# Pulser_AD8331.net
KiCad netlist of a schematic drawn in Altium Designer
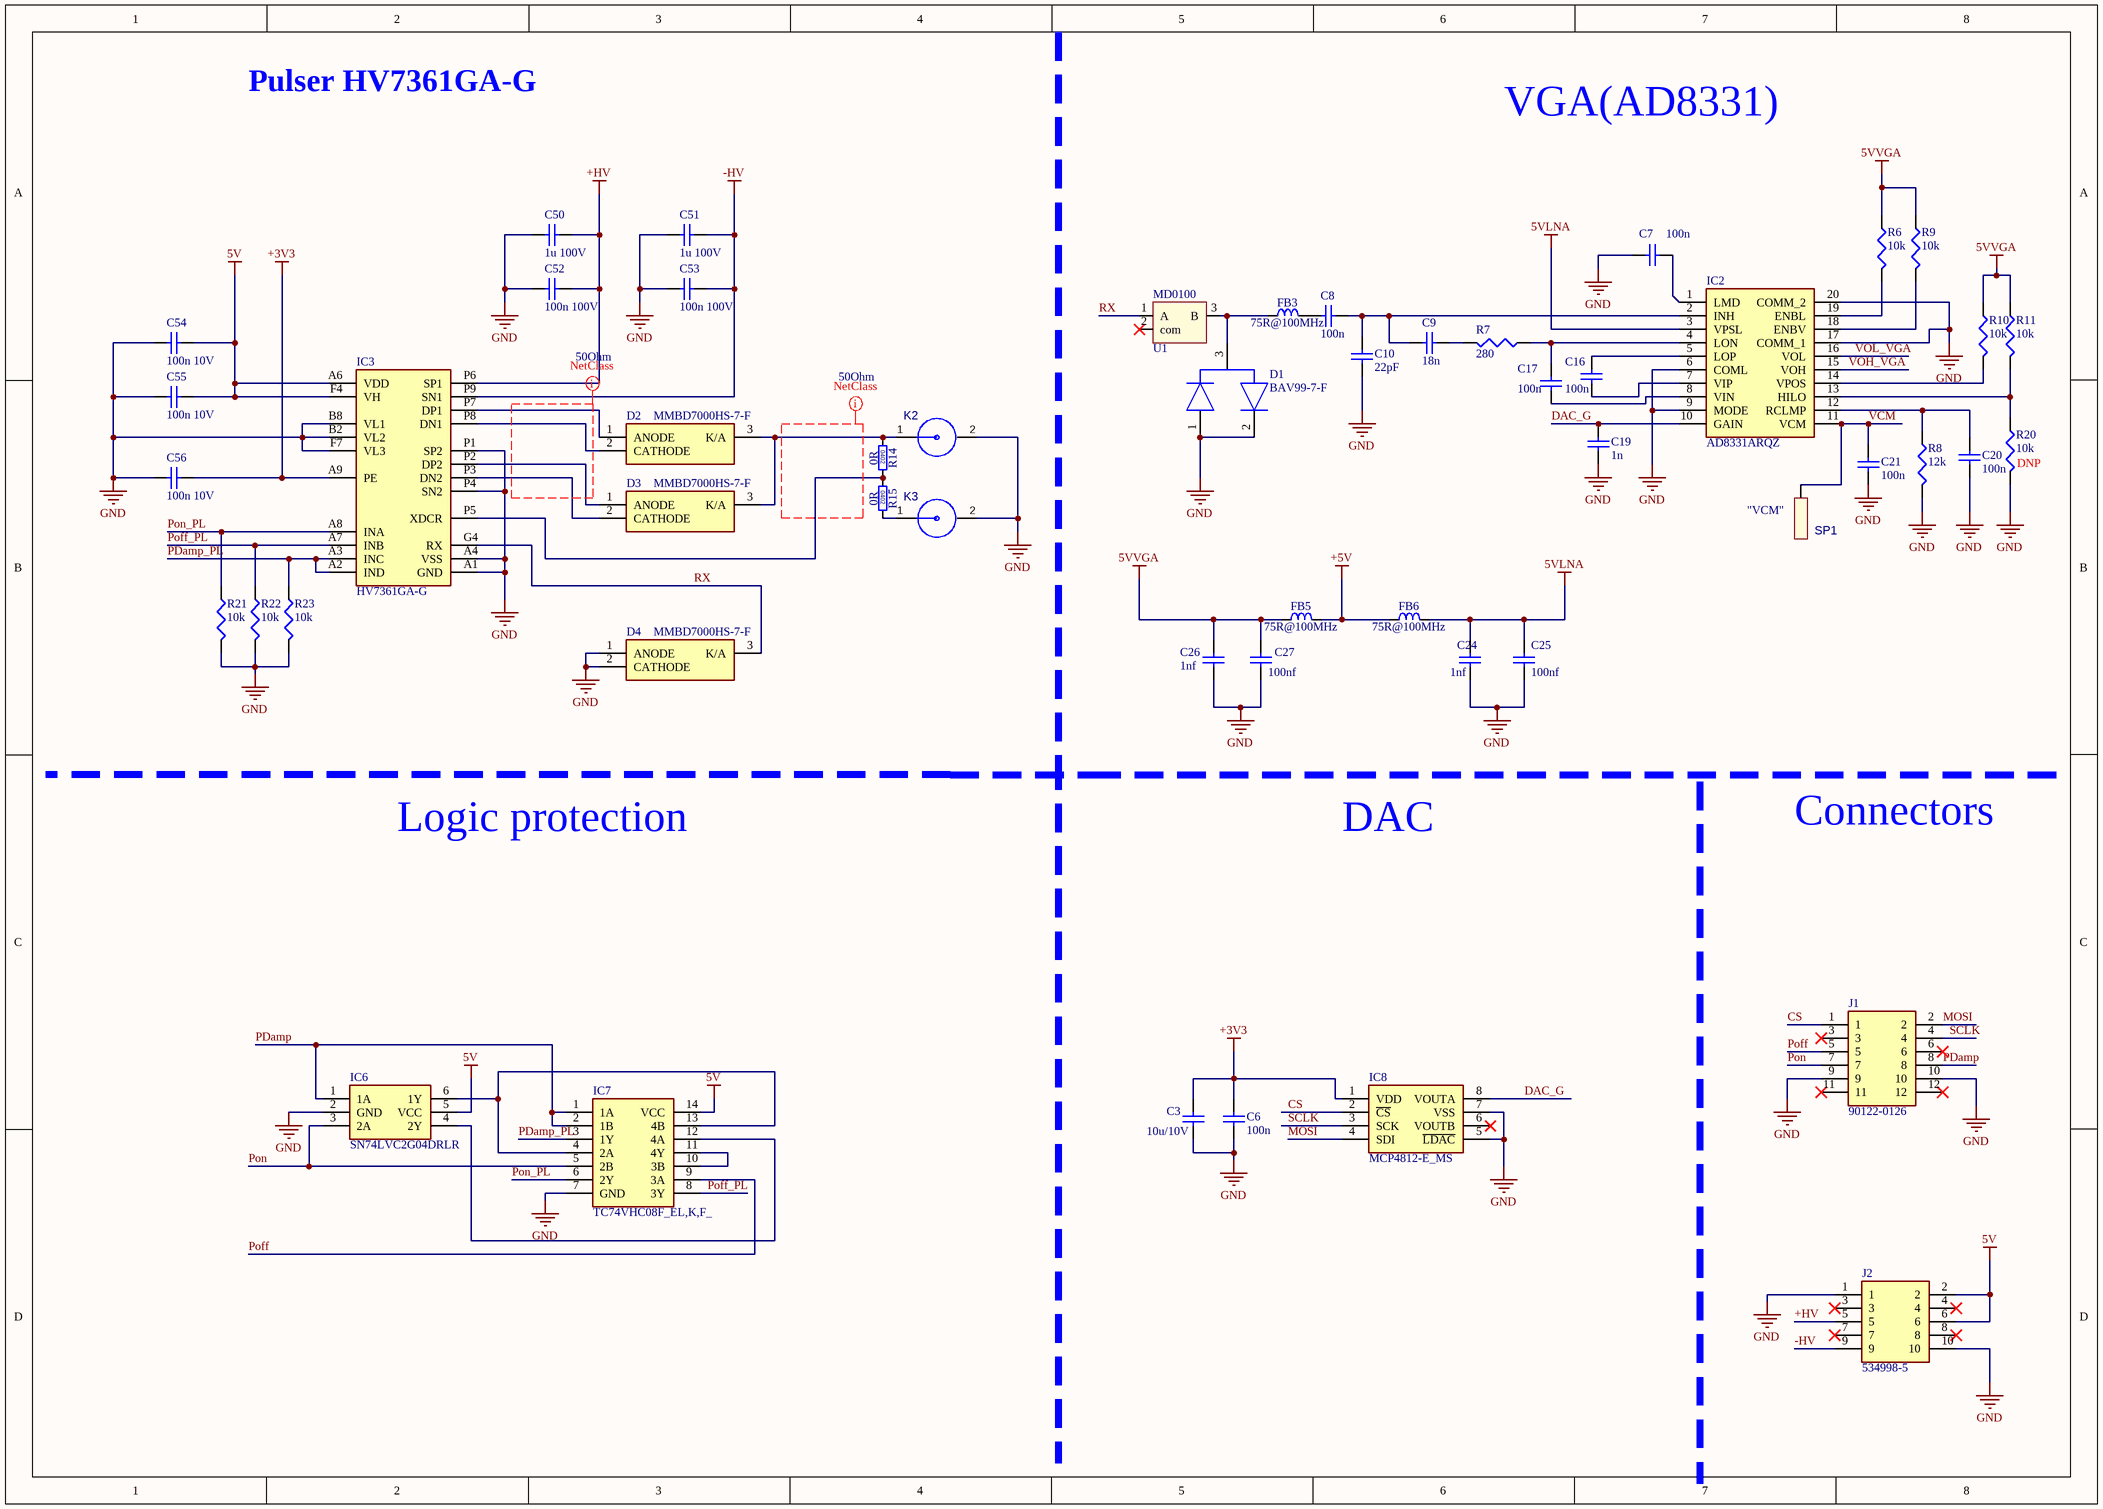
[diagram p0: Pulser & AD8331.SchDoc]

(export (version "E")
  (design (tool "Eeschema 10.0.6"))
  (components
    (comp (ref "C3")
      (value "10u/10V")
      (footprint "0402_C")
      (description "Capacitor  0603 inch")
      (fields (field (name "Comment") "cap0603") (field (name "PUBLISHER") "Altium Limited"))
      (libsource (lib "alt2017") (part "cap0603"))
    )
    (comp (ref "C6")
      (value "100n")
      (footprint "0402_C")
      (description "Capacitor  0402 inch")
      (fields (field (name "Comment") "cap0402") (field (name "PUBLISHER") "Altium Limited"))
      (libsource (lib "alt2017") (part "cap0603"))
    )
    (comp (ref "C7")
      (value "100n")
      (footprint "0402_C")
      (description "Capacitor  0402 inch")
      (fields (field (name "Comment") "cap0402") (field (name "PUBLISHER") "Altium Limited"))
      (libsource (lib "alt2017") (part "cap0603"))
    )
    (comp (ref "C8")
      (value "100n")
      (footprint "0402_C")
      (description "Capacitor  0402 inch")
      (fields (field (name "Comment") "cap0402") (field (name "PUBLISHER") "Altium Limited"))
      (libsource (lib "alt2017") (part "cap0603"))
    )
    (comp (ref "C9")
      (value "18n")
      (footprint "0402_C")
      (description "Capacitor  0402 inch")
      (fields (field (name "Comment") "cap0402") (field (name "PUBLISHER") "Altium Limited"))
      (libsource (lib "alt2017") (part "cap0603"))
    )
    (comp (ref "C10")
      (value "22pF")
      (footprint "0402_C")
      (description "Capacitor  0402 inch")
      (fields (field (name "Comment") "cap0402") (field (name "PUBLISHER") "Altium Limited"))
      (libsource (lib "alt2017") (part "cap0603"))
    )
    (comp (ref "C16")
      (value "100n")
      (footprint "0402_C")
      (description "Capacitor  0402 inch")
      (fields (field (name "Comment") "cap0402") (field (name "PUBLISHER") "Altium Limited"))
      (libsource (lib "alt2017") (part "cap0603"))
    )
    (comp (ref "C17")
      (value "100n")
      (footprint "0402_C")
      (description "Capacitor  0402 inch")
      (fields (field (name "Comment") "cap0402") (field (name "PUBLISHER") "Altium Limited"))
      (libsource (lib "alt2017") (part "cap0603"))
    )
    (comp (ref "C19")
      (value "1n")
      (footprint "0402_C")
      (description "Capacitor  0402 inch")
      (fields (field (name "Comment") "cap0402") (field (name "PUBLISHER") "Altium Limited"))
      (libsource (lib "alt2017") (part "cap0603"))
    )
    (comp (ref "C20")
      (value "100n")
      (footprint "0402_C")
      (description "Capacitor  0402 inch")
      (fields (field (name "Comment") "cap0402") (field (name "PUBLISHER") "Altium Limited"))
      (libsource (lib "alt2017") (part "cap0603"))
    )
    (comp (ref "C21")
      (value "100n")
      (footprint "0402_C")
      (description "Capacitor  0402 inch")
      (fields (field (name "Comment") "cap0402") (field (name "PUBLISHER") "Altium Limited"))
      (libsource (lib "alt2017") (part "cap0603"))
    )
    (comp (ref "C24")
      (value "1nf")
      (footprint "0402_C")
      (description "Capacitor  0603 inch")
      (fields (field (name "Comment") "cap0402") (field (name "PUBLISHER") "Altium Limited"))
      (libsource (lib "alt2017") (part "cap0603"))
    )
    (comp (ref "C25")
      (value "100nf")
      (footprint "0402_C")
      (description "Capacitor  0402 inch")
      (fields (field (name "Comment") "cap0402") (field (name "PUBLISHER") "Altium Limited"))
      (libsource (lib "alt2017") (part "cap0603"))
    )
    (comp (ref "C26")
      (value "1nf")
      (footprint "0402_C")
      (description "Capacitor  0603 inch")
      (fields (field (name "Comment") "cap0402") (field (name "PUBLISHER") "Altium Limited"))
      (libsource (lib "alt2017") (part "cap0603"))
    )
    (comp (ref "C27")
      (value "100nf")
      (footprint "0402_C")
      (description "Capacitor  0402 inch")
      (fields (field (name "Comment") "cap0402") (field (name "PUBLISHER") "Altium Limited"))
      (libsource (lib "alt2017") (part "cap0603"))
    )
    (comp (ref "C50")
      (value "1u 100V")
      (footprint "C0805")
      (description "Capacitor  0603 inch")
      (fields (field (name "Comment") "cap0603") (field (name "PUBLISHER") "Altium Limited"))
      (libsource (lib "alt2017") (part "cap0603"))
    )
    (comp (ref "C51")
      (value "1u 100V")
      (footprint "C0805")
      (description "Capacitor  0603 inch")
      (fields (field (name "Comment") "cap0603") (field (name "PUBLISHER") "Altium Limited"))
      (libsource (lib "alt2017") (part "cap0603"))
    )
    (comp (ref "C52")
      (value "100n 100V")
      (footprint "0402_C")
      (description "Capacitor  0402 inch")
      (fields (field (name "Comment") "cap0402") (field (name "PUBLISHER") "Altium Limited"))
      (libsource (lib "alt2017") (part "cap0603"))
    )
    (comp (ref "C53")
      (value "100n 100V")
      (footprint "0402_C")
      (description "Capacitor  0402 inch")
      (fields (field (name "Comment") "cap0402") (field (name "PUBLISHER") "Altium Limited"))
      (libsource (lib "alt2017") (part "cap0603"))
    )
    (comp (ref "C54")
      (value "100n 10V")
      (footprint "0402_C")
      (description "Capacitor  0402 inch")
      (fields (field (name "Comment") "cap0402") (field (name "PUBLISHER") "Altium Limited"))
      (libsource (lib "alt2017") (part "cap0603"))
    )
    (comp (ref "C55")
      (value "100n 10V")
      (footprint "0402_C")
      (description "Capacitor  0402 inch")
      (fields (field (name "Comment") "cap0402") (field (name "PUBLISHER") "Altium Limited"))
      (libsource (lib "alt2017") (part "cap0603"))
    )
    (comp (ref "C56")
      (value "100n 10V")
      (footprint "0402_C")
      (description "Capacitor  0402 inch")
      (fields (field (name "Comment") "cap0402") (field (name "PUBLISHER") "Altium Limited"))
      (libsource (lib "alt2017") (part "cap0603"))
    )
    (comp (ref "D1")
      (value "BAV99-7-F")
      (footprint "SOT95P240X120-3N")
      (description "Diode")
      (fields (field (name "MOUSER PART NUMBER") "621-BAV99-F"))
      (libsource (lib "*") (part "BAV99-7-F"))
    )
    (comp (ref "D2")
      (value "MMBD7000HS-7-F")
      (footprint "SOT96P240X110-3N_")
      (description "Diode")
      (fields (field (name "MOUSER PART NUMBER") "621-MMBD7000HS-7-F"))
      (libsource (lib "*") (part "MMBD7000HS-7-F"))
    )
    (comp (ref "D3")
      (value "MMBD7000HS-7-F")
      (footprint "SOT96P240X110-3N_")
      (description "Diode")
      (fields (field (name "MOUSER PART NUMBER") "621-MMBD7000HS-7-F"))
      (libsource (lib "*") (part "MMBD7000HS-7-F"))
    )
    (comp (ref "D4")
      (value "MMBD7000HS-7-F")
      (footprint "SOT96P240X110-3N_")
      (description "Diode")
      (fields (field (name "MOUSER PART NUMBER") "621-MMBD7000HS-7-F"))
      (libsource (lib "*") (part "MMBD7000HS-7-F"))
    )
    (comp (ref "FB3")
      (value "75R@100MHz")
      (footprint "SM0603_3D_res")
      (description "chip inductance 0603")
      (fields
        (field (name "PART NUMBER") "IND0805_MURATA_BLM21BB750SN1D")
        (field (name "POWER") "700mA")
        (field (name "AUTHOR") "S. Jafar")
      )
      (libsource (lib "alt_vovan") (part "chip inductance 0603"))
    )
    (comp (ref "FB5")
      (value "75R@100MHz")
      (footprint "SM0603_3D_res")
      (description "chip inductance 0603")
      (fields
        (field (name "PART NUMBER") "IND0805_MURATA_BLM21BB750SN1D")
        (field (name "POWER") "700mA")
        (field (name "AUTHOR") "S. Jafar")
      )
      (libsource (lib "alt_vovan") (part "chip inductance 0603"))
    )
    (comp (ref "FB6")
      (value "75R@100MHz")
      (footprint "SM0603_3D_res")
      (description "chip inductance 0603")
      (fields
        (field (name "PART NUMBER") "IND0805_MURATA_BLM21BB750SN1D")
        (field (name "POWER") "700mA")
        (field (name "AUTHOR") "S. Jafar")
      )
      (libsource (lib "alt_vovan") (part "chip inductance 0603"))
    )
    (comp (ref "IC2")
      (value "AD8331ARQZ")
      (footprint "SOP64P600X175-20N")
      (description "Integrated Circuit")
      (fields (field (name "MOUSER PART NUMBER") "584-AD8331ARQZ"))
      (libsource (lib "*") (part "AD8331ARQZ"))
    )
    (comp (ref "IC3")
      (value "HV7361GA-G")
      (footprint "shunt_resistor:BGA22C50P9X14_500X700X105")
      (description "Integrated Circuit")
      (fields (field (name "MOUSER PART NUMBER") "579-HV7361GA-G"))
      (libsource (lib "Lib") (part "HV7361GA-G"))
    )
    (comp (ref "IC6")
      (value "SN74LVC2G04DRLR")
      (footprint "shunt_resistor:SOTFL50P160X60-6N")
      (description "Integrated Circuit")
      (fields (field (name "MOUSER PART NUMBER") "595-SN74LVC2G04DRLR"))
      (libsource (lib "shunt_resistor") (part "SN74LVC2G04DRLR"))
    )
    (comp (ref "IC7")
      (value "TC74VHC08F_EL,K,F_")
      (footprint "SOIC127P780X190-14N_")
      (description "Hardware")
      (fields
        (field (name "MANUFACTURER_PART_NUMBER") "TC74VHC08F(EL,K,F)")
        (field (name "MOUSER PART NUMBER") "757-TC74VHC08FELKF")
      )
      (libsource (lib "shunt_resistor") (part "TC74VHC08F_EL,K,F_"))
    )
    (comp (ref "IC8")
      (value "MCP4812-E_MS")
      (footprint "shunt_resistor:SOP65P490X110-8N")
      (description "Integrated Circuit")
      (fields
        (field (name "MANUFACTURER_PART_NUMBER") "MCP4812-E/MS")
        (field (name "MOUSER PART NUMBER") "579-MCP4812-E/MS")
      )
      (libsource (lib "*") (part "MCP4812-E_MS"))
    )
    (comp (ref "J1")
      (value "90122-0126")
      (footprint "shunt_resistor:HDRRA12W65P254_2X6_1516X250X615P")
      (description "Connector")
      (fields (field (name "MOUSER PART NUMBER") "538-90122-0126"))
      (libsource (lib "*") (part "90122-0126"))
    )
    (comp (ref "J2")
      (value "534998-5")
      (footprint "shunt_resistor:RHDR10W77P254X254_2X5_1270X503X635P")
      (description "Connector")
      (fields (field (name "MOUSER PART NUMBER") "571-5349985"))
      (libsource (lib "*") (part "534998-5"))
    )
    (comp (ref "K2")
      (value "SMA_Edge")
      (footprint "AMPHENOL_132357-11")
      (libsource (lib "alt_vovan") (part "SMA_Edge"))
    )
    (comp (ref "K3")
      (value "SMA_Edge")
      (footprint "AMPHENOL_132357-11")
      (libsource (lib "alt_vovan") (part "SMA_Edge"))
    )
    (comp (ref "R6")
      (value "10k")
      (footprint "0402_R")
      (description "RES 10K OHM 1/16W 1% 0402 SMD")
      (libsource (lib "Integrated_Library_RF_FEB_2012") (part "RC0402FR-0710KL"))
    )
    (comp (ref "R7")
      (value "280")
      (footprint "0402_R")
      (description "RES 280 OHM 1/16W 0402 SMD")
      (libsource (lib "Integrated_Library_RF_FEB_2012") (part "RC0402FR-0710KL"))
    )
    (comp (ref "R8")
      (value "12k")
      (footprint "0402_R")
      (description "RES 12K OHM 1/16W 0402 SMD")
      (libsource (lib "Integrated_Library_RF_FEB_2012") (part "RC0402FR-0710KL"))
    )
    (comp (ref "R9")
      (value "10k")
      (footprint "0402_R")
      (description "RES 10K OHM 1/16W 1% 0402 SMD")
      (libsource (lib "Integrated_Library_RF_FEB_2012") (part "RC0402FR-0710KL"))
    )
    (comp (ref "R10")
      (value "10k")
      (footprint "0402_R")
      (description "RES 10K OHM 1/16W 1% 0402 SMD")
      (libsource (lib "Integrated_Library_RF_FEB_2012") (part "RC0402FR-0710KL"))
    )
    (comp (ref "R11")
      (value "10k")
      (footprint "0402_R")
      (description "RES 10K OHM 1/16W 1% 0402 SMD")
      (libsource (lib "Integrated_Library_RF_FEB_2012") (part "RC0402FR-0710KL"))
    )
    (comp (ref "R14")
      (value "0R")
      (footprint "0402_R")
      (description "Res_0402_EU")
      (fields
        (field (name "PART NUMBER") "R1206_4K7_1%_0.25W_100PPM")
        (field (name "POWER") "0.25W")
        (field (name "AUTHOR") "CERN DEM JLC")
      )
      (libsource (lib "alt_vovan") (part "Res_0402_EU"))
    )
    (comp (ref "R15")
      (value "0R")
      (footprint "0402_R")
      (description "Res_0402_EU")
      (fields
        (field (name "PART NUMBER") "R1206_4K7_1%_0.25W_100PPM")
        (field (name "POWER") "0.25W")
        (field (name "AUTHOR") "CERN DEM JLC")
      )
      (libsource (lib "alt_vovan") (part "Res_0402_EU"))
    )
    (comp (ref "R20")
      (value "10k")
      (footprint "0402_R")
      (description "RES 10K OHM 1/16W 1% 0402 SMD")
      (libsource (lib "Integrated_Library_RF_FEB_2012") (part "RC0402FR-0710KL"))
    )
    (comp (ref "R21")
      (value "10k")
      (footprint "0402_R")
      (description "RES 10K OHM 1/16W 1% 0402 SMD")
      (libsource (lib "Integrated_Library_RF_FEB_2012") (part "RC0402FR-0710KL"))
    )
    (comp (ref "R22")
      (value "10k")
      (footprint "0402_R")
      (description "RES 10K OHM 1/16W 1% 0402 SMD")
      (libsource (lib "Integrated_Library_RF_FEB_2012") (part "RC0402FR-0710KL"))
    )
    (comp (ref "R23")
      (value "10k")
      (footprint "0402_R")
      (description "RES 10K OHM 1/16W 1% 0402 SMD")
      (libsource (lib "Integrated_Library_RF_FEB_2012") (part "RC0402FR-0710KL"))
    )
    (comp (ref "SP1")
      (value "\"VCM\"")
      (footprint "SolderPad_D1mm _round")
      (description "for finger touch")
      (fields (field (name "Comment") "SolderPad D1mm_round"))
      (libsource (lib "alt2017") (part "SolderPad D1mm_round"))
    )
    (comp (ref "U1")
      (value "T/R switch")
      (footprint "SOT89-150P409X160-3N")
      (libsource (lib "alt_vovan") (part "MD0100N8-G"))
    )
  )
  (nets
    (net (code "1") (name "+3V3") (class "Default")
      (node (ref "C3") (pin "1") (pinfunction "1_1") (pintype "passive"))
      (node (ref "C56") (pin "1") (pinfunction "1_1") (pintype "passive"))
      (node (ref "C6") (pin "1") (pinfunction "1_1") (pintype "passive"))
      (node (ref "IC3") (pin "A9") (pinfunction "PE_A9") (pintype "passive"))
      (node (ref "IC8") (pin "1") (pinfunction "VDD_1") (pintype "passive"))
    )
    (net (code "2") (name "+5V") (class "Default")
      (node (ref "FB5") (pin "2") (pinfunction "2_2") (pintype "passive"))
      (node (ref "FB6") (pin "1") (pinfunction "1_1") (pintype "passive"))
    )
    (net (code "3") (name "+HV") (class "Default")
      (node (ref "C50") (pin "1") (pinfunction "1_1") (pintype "passive"))
      (node (ref "C52") (pin "2") (pinfunction "2_2") (pintype "passive"))
      (node (ref "IC3") (pin "P6") (pinfunction "SP1_P6") (pintype "passive"))
      (node (ref "J2") (pin "5") (pinfunction "5_5") (pintype "passive"))
    )
    (net (code "4") (name "-HV") (class "Default")
      (node (ref "C51") (pin "1") (pinfunction "1_1") (pintype "passive"))
      (node (ref "C53") (pin "2") (pinfunction "2_2") (pintype "passive"))
      (node (ref "IC3") (pin "P9") (pinfunction "SN1_P9") (pintype "passive"))
      (node (ref "J2") (pin "9") (pinfunction "9_9") (pintype "passive"))
    )
    (net (code "5") (name "/CS") (class "Default")
      (node (ref "IC8") (pin "2") (pinfunction "~{CS}_2") (pintype "passive"))
      (node (ref "J1") (pin "1") (pinfunction "1_1") (pintype "passive"))
    )
    (net (code "6") (name "/DAC_G") (class "Default")
      (node (ref "C19") (pin "2") (pinfunction "2_2") (pintype "passive"))
      (node (ref "IC2") (pin "10") (pinfunction "GAIN_10") (pintype "passive"))
      (node (ref "IC8") (pin "8") (pinfunction "VOUTA_8") (pintype "passive"))
    )
    (net (code "7") (name "/MOSI") (class "Default")
      (node (ref "IC8") (pin "4") (pinfunction "SDI_4") (pintype "passive"))
      (node (ref "J1") (pin "2") (pinfunction "2_2") (pintype "passive"))
    )
    (net (code "8") (name "/PDamp") (class "Default")
      (node (ref "IC6") (pin "1") (pinfunction "1A_1") (pintype "passive"))
      (node (ref "IC7") (pin "1") (pinfunction "1A_1") (pintype "passive"))
      (node (ref "IC7") (pin "2") (pinfunction "1B_2") (pintype "passive"))
      (node (ref "J1") (pin "8") (pinfunction "8_8") (pintype "passive"))
    )
    (net (code "9") (name "/PDamp_PL") (class "Default")
      (node (ref "IC3") (pin "A2") (pinfunction "IND_A2") (pintype "passive"))
      (node (ref "IC3") (pin "A3") (pinfunction "INC_A3") (pintype "passive"))
      (node (ref "IC7") (pin "3") (pinfunction "1Y_3") (pintype "passive"))
      (node (ref "R23") (pin "1") (pinfunction "1_1") (pintype "passive"))
    )
    (net (code "10") (name "/Poff") (class "Default")
      (node (ref "IC7") (pin "9") (pinfunction "3A_9") (pintype "passive"))
      (node (ref "J1") (pin "5") (pinfunction "5_5") (pintype "passive"))
    )
    (net (code "11") (name "/Poff_PL") (class "Default")
      (node (ref "IC3") (pin "A7") (pinfunction "INB_A7") (pintype "passive"))
      (node (ref "IC7") (pin "8") (pinfunction "3Y_8") (pintype "passive"))
      (node (ref "R22") (pin "1") (pinfunction "1_1") (pintype "passive"))
    )
    (net (code "12") (name "/Pon") (class "Default")
      (node (ref "IC6") (pin "3") (pinfunction "2A_3") (pintype "passive"))
      (node (ref "IC7") (pin "5") (pinfunction "2B_5") (pintype "passive"))
      (node (ref "J1") (pin "7") (pinfunction "7_7") (pintype "passive"))
    )
    (net (code "13") (name "/Pon_PL") (class "Default")
      (node (ref "IC3") (pin "A8") (pinfunction "INA_A8") (pintype "passive"))
      (node (ref "IC7") (pin "6") (pinfunction "2Y_6") (pintype "passive"))
      (node (ref "R21") (pin "1") (pinfunction "1_1") (pintype "passive"))
    )
    (net (code "14") (name "/RX") (class "Default")
      (node (ref "D4") (pin "3") (pinfunction "K/A_3") (pintype "passive"))
      (node (ref "IC3") (pin "G4") (pinfunction "RX_G4") (pintype "passive"))
      (node (ref "U1") (pin "1") (pinfunction "A_1") (pintype "passive"))
    )
    (net (code "15") (name "/SCLK") (class "Default")
      (node (ref "IC8") (pin "3") (pinfunction "SCK_3") (pintype "passive"))
      (node (ref "J1") (pin "4") (pinfunction "4_4") (pintype "passive"))
    )
    (net (code "16") (name "/VCM") (class "Default")
      (node (ref "C21") (pin "1") (pinfunction "1_1") (pintype "passive"))
      (node (ref "IC2") (pin "11") (pinfunction "VCM_11") (pintype "passive"))
      (node (ref "SP1") (pin "1") (pinfunction "1_1") (pintype "passive"))
    )
    (net (code "17") (name "/VOH_VGA") (class "Default")
      (node (ref "IC2") (pin "15") (pinfunction "VOH_15") (pintype "passive"))
    )
    (net (code "18") (name "/VOL_VGA") (class "Default")
      (node (ref "IC2") (pin "16") (pinfunction "VOL_16") (pintype "passive"))
    )
    (net (code "19") (name "5V") (class "Default")
      (node (ref "C54") (pin "1") (pinfunction "1_1") (pintype "passive"))
      (node (ref "C55") (pin "1") (pinfunction "1_1") (pintype "passive"))
      (node (ref "IC3") (pin "A6") (pinfunction "VDD_A6") (pintype "passive"))
      (node (ref "IC3") (pin "F4") (pinfunction "VH_F4") (pintype "passive"))
      (node (ref "IC6") (pin "5") (pinfunction "VCC_5") (pintype "passive"))
      (node (ref "IC7") (pin "14") (pinfunction "VCC_14") (pintype "power_in"))
      (node (ref "J2") (pin "2") (pinfunction "2_2") (pintype "passive"))
      (node (ref "J2") (pin "6") (pinfunction "6_6") (pintype "passive"))
    )
    (net (code "20") (name "5VLNA") (class "Default")
      (node (ref "C24") (pin "2") (pinfunction "2_2") (pintype "passive"))
      (node (ref "C25") (pin "2") (pinfunction "2_2") (pintype "passive"))
      (node (ref "FB6") (pin "2") (pinfunction "2_2") (pintype "passive"))
      (node (ref "IC2") (pin "3") (pinfunction "VPSL_3") (pintype "passive"))
    )
    (net (code "21") (name "5VVGA") (class "Default")
      (node (ref "C26") (pin "2") (pinfunction "2_2") (pintype "passive"))
      (node (ref "C27") (pin "2") (pinfunction "2_2") (pintype "passive"))
      (node (ref "FB5") (pin "1") (pinfunction "1_1") (pintype "passive"))
      (node (ref "R10") (pin "1") (pinfunction "1_1") (pintype "passive"))
      (node (ref "R11") (pin "1") (pinfunction "1_1") (pintype "passive"))
      (node (ref "R6") (pin "1") (pinfunction "1_1") (pintype "passive"))
      (node (ref "R9") (pin "1") (pinfunction "1_1") (pintype "passive"))
    )
    (net (code "22") (name "GND") (class "Default")
      (node (ref "C10") (pin "1") (pinfunction "1_1") (pintype "passive"))
      (node (ref "C19") (pin "1") (pinfunction "1_1") (pintype "passive"))
      (node (ref "C20") (pin "1") (pinfunction "1_1") (pintype "passive"))
      (node (ref "C21") (pin "2") (pinfunction "2_2") (pintype "passive"))
      (node (ref "C24") (pin "1") (pinfunction "1_1") (pintype "passive"))
      (node (ref "C25") (pin "1") (pinfunction "1_1") (pintype "passive"))
      (node (ref "C26") (pin "1") (pinfunction "1_1") (pintype "passive"))
      (node (ref "C27") (pin "1") (pinfunction "1_1") (pintype "passive"))
      (node (ref "C3") (pin "2") (pinfunction "2_2") (pintype "passive"))
      (node (ref "C50") (pin "2") (pinfunction "2_2") (pintype "passive"))
      (node (ref "C51") (pin "2") (pinfunction "2_2") (pintype "passive"))
      (node (ref "C52") (pin "1") (pinfunction "1_1") (pintype "passive"))
      (node (ref "C53") (pin "1") (pinfunction "1_1") (pintype "passive"))
      (node (ref "C54") (pin "2") (pinfunction "2_2") (pintype "passive"))
      (node (ref "C55") (pin "2") (pinfunction "2_2") (pintype "passive"))
      (node (ref "C56") (pin "2") (pinfunction "2_2") (pintype "passive"))
      (node (ref "C6") (pin "2") (pinfunction "2_2") (pintype "passive"))
      (node (ref "C7") (pin "1") (pinfunction "1_1") (pintype "passive"))
      (node (ref "D1") (pin "1") (pinfunction "ANODE_1") (pintype "passive"))
      (node (ref "D1") (pin "2") (pinfunction "CATHODE_2") (pintype "passive"))
      (node (ref "D4") (pin "1") (pinfunction "ANODE_1") (pintype "passive"))
      (node (ref "D4") (pin "2") (pinfunction "CATHODE_2") (pintype "passive"))
      (node (ref "IC2") (pin "17") (pinfunction "COMM_1_17") (pintype "passive"))
      (node (ref "IC2") (pin "20") (pinfunction "COMM_2_20") (pintype "passive"))
      (node (ref "IC2") (pin "6") (pinfunction "COML_6") (pintype "passive"))
      (node (ref "IC2") (pin "9") (pinfunction "MODE_9") (pintype "passive"))
      (node (ref "IC3") (pin "A1") (pinfunction "GND_A1") (pintype "passive"))
      (node (ref "IC3") (pin "A4") (pinfunction "VSS_A4") (pintype "passive"))
      (node (ref "IC3") (pin "B2") (pinfunction "VL2_B2") (pintype "passive"))
      (node (ref "IC3") (pin "B8") (pinfunction "VL1_B8") (pintype "passive"))
      (node (ref "IC3") (pin "F7") (pinfunction "VL3_F7") (pintype "passive"))
      (node (ref "IC3") (pin "P1") (pinfunction "SP2_P1") (pintype "passive"))
      (node (ref "IC3") (pin "P4") (pinfunction "SN2_P4") (pintype "passive"))
      (node (ref "IC6") (pin "2") (pinfunction "GND_2") (pintype "passive"))
      (node (ref "IC7") (pin "7") (pinfunction "GND_7") (pintype "power_in"))
      (node (ref "IC8") (pin "5") (pinfunction "~{LDAC}_5") (pintype "passive"))
      (node (ref "IC8") (pin "7") (pinfunction "VSS_7") (pintype "passive"))
      (node (ref "J1") (pin "10") (pinfunction "10_10") (pintype "passive"))
      (node (ref "J1") (pin "9") (pinfunction "9_9") (pintype "passive"))
      (node (ref "J2") (pin "1") (pinfunction "1_1") (pintype "passive"))
      (node (ref "J2") (pin "10") (pinfunction "10_10") (pintype "passive"))
      (node (ref "K2") (pin "2") (pinfunction "2_2") (pintype "passive"))
      (node (ref "K3") (pin "2") (pinfunction "2_2") (pintype "passive"))
      (node (ref "R20") (pin "2") (pinfunction "2_2") (pintype "passive"))
      (node (ref "R21") (pin "2") (pinfunction "2_2") (pintype "passive"))
      (node (ref "R22") (pin "2") (pinfunction "2_2") (pintype "passive"))
      (node (ref "R23") (pin "2") (pinfunction "2_2") (pintype "passive"))
      (node (ref "R8") (pin "2") (pinfunction "2_2") (pintype "passive"))
    )
    (net (code "23") (name "Net-(C8-Pad1)") (class "Default")
      (node (ref "C8") (pin "1") (pinfunction "1_1") (pintype "passive"))
      (node (ref "FB3") (pin "2") (pinfunction "2_2") (pintype "passive"))
    )
    (net (code "24") (name "Net-(C9-Pad1)") (class "Default")
      (node (ref "C9") (pin "1") (pinfunction "1_1") (pintype "passive"))
      (node (ref "R7") (pin "2") (pinfunction "2_2") (pintype "passive"))
    )
    (net (code "25") (name "Net-(D1-A{slash}K)") (class "Default")
      (node (ref "D1") (pin "3") (pinfunction "A/K_3") (pintype "passive"))
      (node (ref "FB3") (pin "1") (pinfunction "1_1") (pintype "passive"))
      (node (ref "U1") (pin "3") (pinfunction "B_3") (pintype "passive"))
    )
    (net (code "26") (name "Net-(D2-ANODE)") (class "Default")
      (node (ref "D2") (pin "1") (pinfunction "ANODE_1") (pintype "passive"))
      (node (ref "IC3") (pin "P7") (pinfunction "DP1_P7") (pintype "passive"))
    )
    (net (code "27") (name "Net-(D2-CATHODE)") (class "Default")
      (node (ref "D2") (pin "2") (pinfunction "CATHODE_2") (pintype "passive"))
      (node (ref "IC3") (pin "P8") (pinfunction "DN1_P8") (pintype "passive"))
    )
    (net (code "28") (name "Net-(D2-K{slash}A)") (class "Default")
      (node (ref "D2") (pin "3") (pinfunction "K/A_3") (pintype "passive"))
      (node (ref "D3") (pin "3") (pinfunction "K/A_3") (pintype "passive"))
      (node (ref "K2") (pin "1") (pinfunction "1_1") (pintype "passive"))
      (node (ref "R14") (pin "1") (pinfunction "1_1") (pintype "passive"))
    )
    (net (code "29") (name "Net-(D3-ANODE)") (class "Default")
      (node (ref "D3") (pin "1") (pinfunction "ANODE_1") (pintype "passive"))
      (node (ref "IC3") (pin "P2") (pinfunction "DP2_P2") (pintype "passive"))
    )
    (net (code "30") (name "Net-(D3-CATHODE)") (class "Default")
      (node (ref "D3") (pin "2") (pinfunction "CATHODE_2") (pintype "passive"))
      (node (ref "IC3") (pin "P3") (pinfunction "DN2_P3") (pintype "passive"))
    )
    (net (code "31") (name "Net-(IC2-ENBL)") (class "Default")
      (node (ref "IC2") (pin "19") (pinfunction "ENBL_19") (pintype "passive"))
      (node (ref "R6") (pin "2") (pinfunction "2_2") (pintype "passive"))
    )
    (net (code "32") (name "Net-(IC2-ENBV)") (class "Default")
      (node (ref "IC2") (pin "18") (pinfunction "ENBV_18") (pintype "passive"))
      (node (ref "R9") (pin "2") (pinfunction "2_2") (pintype "passive"))
    )
    (net (code "33") (name "Net-(IC2-HILO)") (class "Default")
      (node (ref "IC2") (pin "13") (pinfunction "HILO_13") (pintype "passive"))
      (node (ref "R11") (pin "2") (pinfunction "2_2") (pintype "passive"))
      (node (ref "R20") (pin "1") (pinfunction "1_1") (pintype "passive"))
    )
    (net (code "34") (name "Net-(IC2-INH)") (class "Default")
      (node (ref "C10") (pin "2") (pinfunction "2_2") (pintype "passive"))
      (node (ref "C8") (pin "2") (pinfunction "2_2") (pintype "passive"))
      (node (ref "C9") (pin "2") (pinfunction "2_2") (pintype "passive"))
      (node (ref "IC2") (pin "2") (pinfunction "INH_2") (pintype "passive"))
    )
    (net (code "35") (name "Net-(IC2-LMD)") (class "Default")
      (node (ref "C7") (pin "2") (pinfunction "2_2") (pintype "passive"))
      (node (ref "IC2") (pin "1") (pinfunction "LMD_1") (pintype "passive"))
    )
    (net (code "36") (name "Net-(IC2-LON)") (class "Default")
      (node (ref "C17") (pin "2") (pinfunction "2_2") (pintype "passive"))
      (node (ref "IC2") (pin "4") (pinfunction "LON_4") (pintype "passive"))
      (node (ref "R7") (pin "1") (pinfunction "1_1") (pintype "passive"))
    )
    (net (code "37") (name "Net-(IC2-LOP)") (class "Default")
      (node (ref "C16") (pin "2") (pinfunction "2_2") (pintype "passive"))
      (node (ref "IC2") (pin "5") (pinfunction "LOP_5") (pintype "passive"))
    )
    (net (code "38") (name "Net-(IC2-RCLMP)") (class "Default")
      (node (ref "C20") (pin "2") (pinfunction "2_2") (pintype "passive"))
      (node (ref "IC2") (pin "12") (pinfunction "RCLMP_12") (pintype "passive"))
      (node (ref "R8") (pin "1") (pinfunction "1_1") (pintype "passive"))
    )
    (net (code "39") (name "Net-(IC2-VIN)") (class "Default")
      (node (ref "C17") (pin "1") (pinfunction "1_1") (pintype "passive"))
      (node (ref "IC2") (pin "8") (pinfunction "VIN_8") (pintype "passive"))
    )
    (net (code "40") (name "Net-(IC2-VIP)") (class "Default")
      (node (ref "C16") (pin "1") (pinfunction "1_1") (pintype "passive"))
      (node (ref "IC2") (pin "7") (pinfunction "VIP_7") (pintype "passive"))
    )
    (net (code "41") (name "Net-(IC2-VPOS)") (class "Default")
      (node (ref "IC2") (pin "14") (pinfunction "VPOS_14") (pintype "passive"))
      (node (ref "R10") (pin "2") (pinfunction "2_2") (pintype "passive"))
    )
    (net (code "42") (name "Net-(IC3-XDCR)") (class "Default")
      (node (ref "IC3") (pin "P5") (pinfunction "XDCR_P5") (pintype "passive"))
      (node (ref "R14") (pin "2") (pinfunction "2_2") (pintype "passive"))
      (node (ref "R15") (pin "1") (pinfunction "1_1") (pintype "passive"))
    )
    (net (code "43") (name "Net-(IC6-1Y)") (class "Default")
      (node (ref "IC6") (pin "6") (pinfunction "1Y_6") (pintype "passive"))
      (node (ref "IC7") (pin "13") (pinfunction "4B_13") (pintype "passive"))
      (node (ref "IC7") (pin "4") (pinfunction "2A_4") (pintype "passive"))
    )
    (net (code "44") (name "Net-(IC6-2Y)") (class "Default")
      (node (ref "IC6") (pin "4") (pinfunction "2Y_4") (pintype "passive"))
      (node (ref "IC7") (pin "12") (pinfunction "4A_12") (pintype "passive"))
    )
    (net (code "45") (name "Net-(IC7-3B)") (class "Default")
      (node (ref "IC7") (pin "10") (pinfunction "3B_10") (pintype "passive"))
      (node (ref "IC7") (pin "11") (pinfunction "4Y_11") (pintype "passive"))
    )
    (net (code "46") (name "Net-(K3-Pad1)") (class "Default")
      (node (ref "K3") (pin "1") (pinfunction "1_1") (pintype "passive"))
      (node (ref "R15") (pin "2") (pinfunction "2_2") (pintype "passive"))
    )
    (net (code "47") (name "unconnected-(IC8-VOUTB-Pad6)") (class "Default")
      (node (ref "IC8") (pin "6") (pinfunction "VOUTB_6") (pintype "passive+no_connect"))
    )
    (net (code "48") (name "unconnected-(J1-Pad3)") (class "Default")
      (node (ref "J1") (pin "3") (pinfunction "3_3") (pintype "passive+no_connect"))
    )
    (net (code "49") (name "unconnected-(J1-Pad6)") (class "Default")
      (node (ref "J1") (pin "6") (pinfunction "6_6") (pintype "passive+no_connect"))
    )
    (net (code "50") (name "unconnected-(J1-Pad11)") (class "Default")
      (node (ref "J1") (pin "11") (pinfunction "11_11") (pintype "passive+no_connect"))
    )
    (net (code "51") (name "unconnected-(J1-Pad12)") (class "Default")
      (node (ref "J1") (pin "12") (pinfunction "12_12") (pintype "passive+no_connect"))
    )
    (net (code "52") (name "unconnected-(J2-Pad3)") (class "Default")
      (node (ref "J2") (pin "3") (pinfunction "3_3") (pintype "passive+no_connect"))
    )
    (net (code "53") (name "unconnected-(J2-Pad4)") (class "Default")
      (node (ref "J2") (pin "4") (pinfunction "4_4") (pintype "passive+no_connect"))
    )
    (net (code "54") (name "unconnected-(J2-Pad7)") (class "Default")
      (node (ref "J2") (pin "7") (pinfunction "7_7") (pintype "passive+no_connect"))
    )
    (net (code "55") (name "unconnected-(J2-Pad8)") (class "Default")
      (node (ref "J2") (pin "8") (pinfunction "8_8") (pintype "passive+no_connect"))
    )
    (net (code "56") (name "unconnected-(U1-com-Pad2)") (class "Default")
      (node (ref "U1") (pin "2") (pinfunction "com_2") (pintype "passive+no_connect"))
    )
  )
)
